# LooRollSensorMiddleBoard.net
KiCad netlist of a schematic drawn in EAGLE
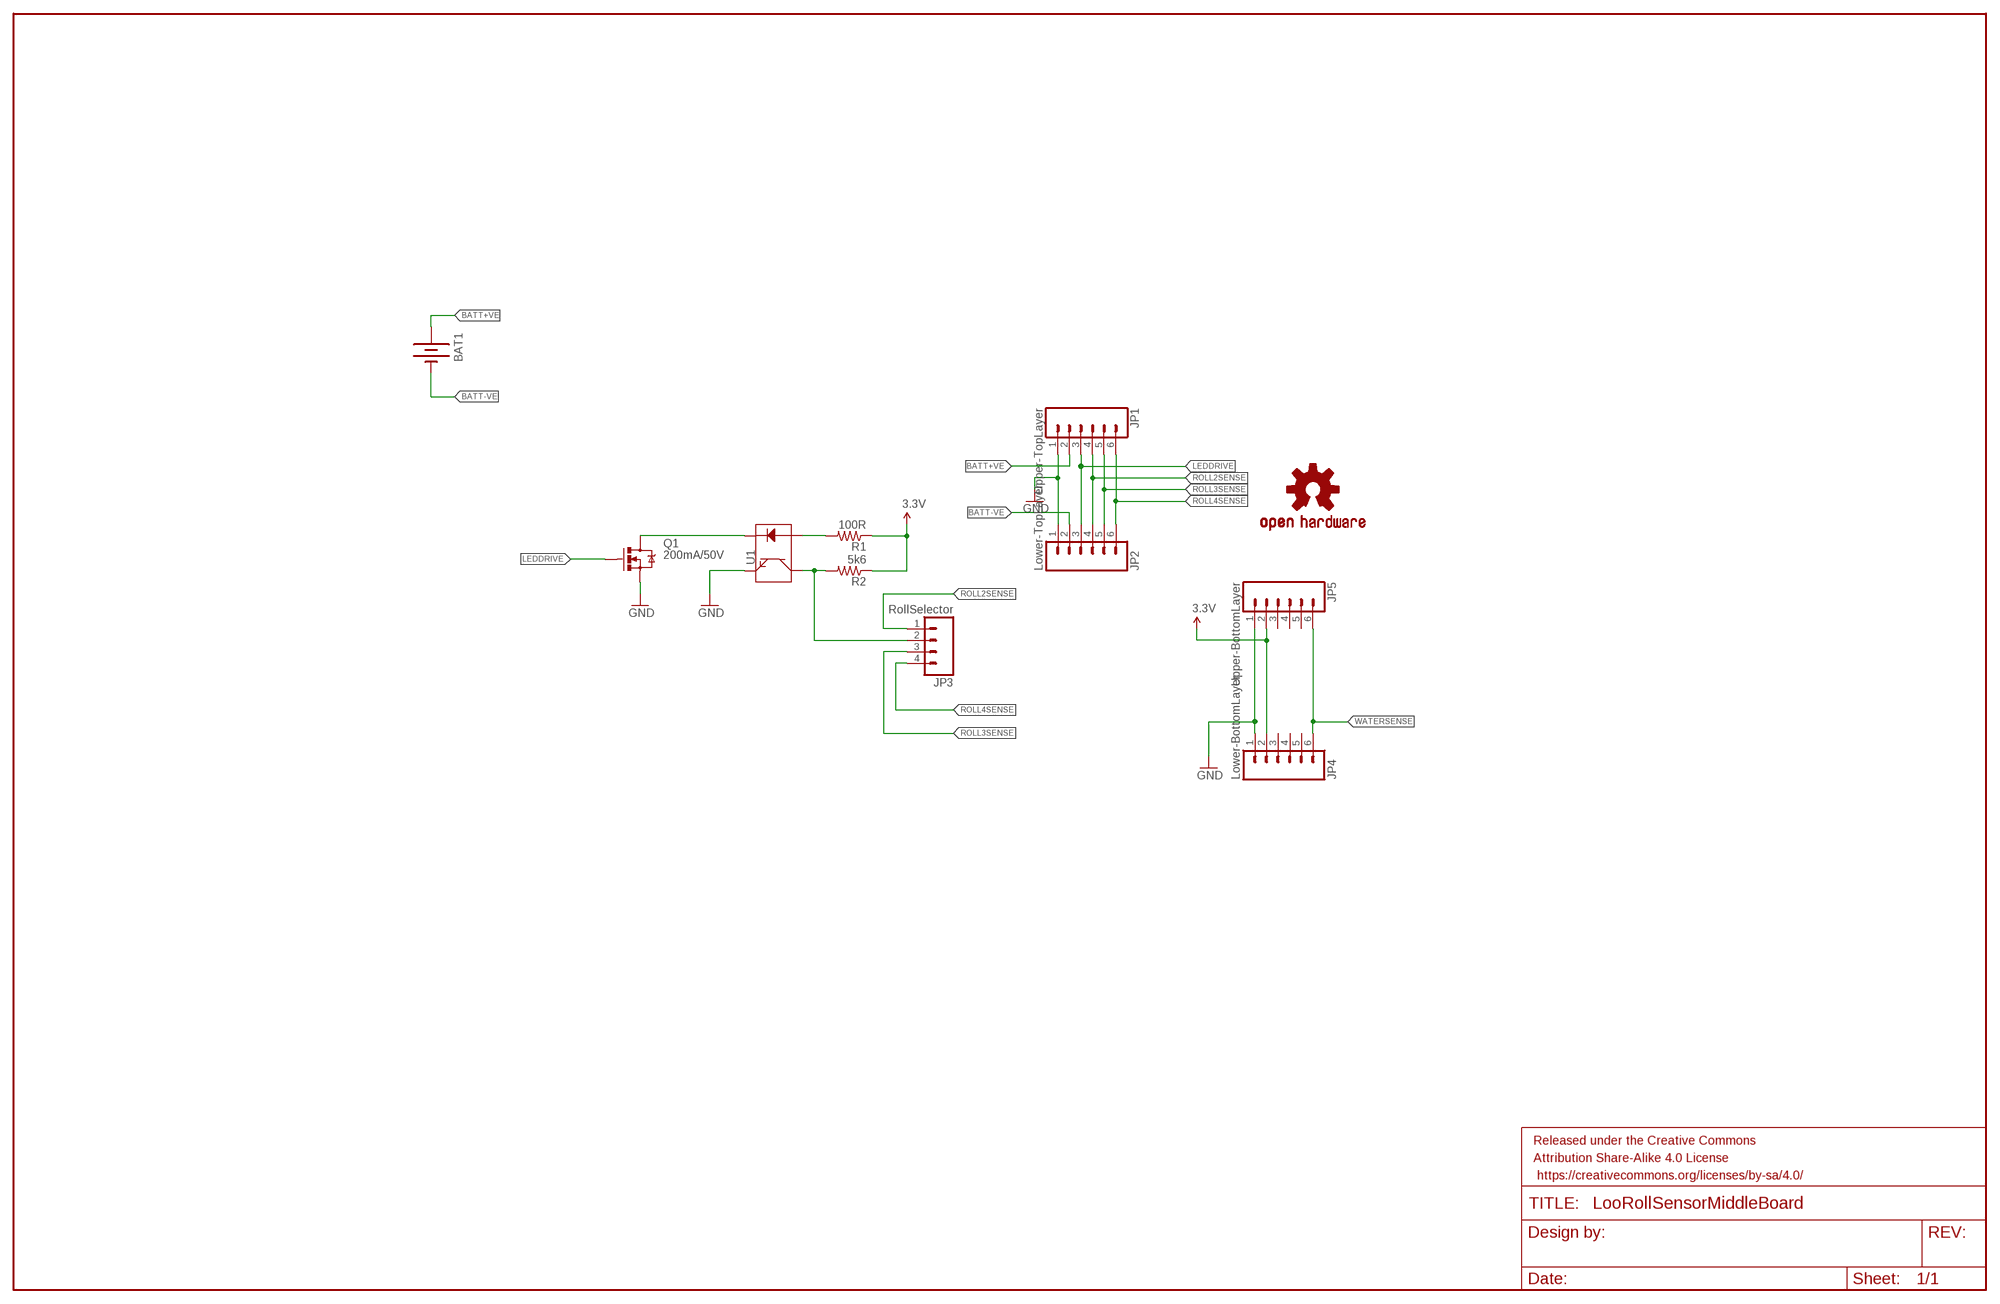
[diagram p0: schematic, sheet 1]

(export (version "E")
  (design (tool "Eeschema 10.0.6"))
  (components
    (comp (ref "BAT1")
      (value "BATTERYAA-PANEL")
      (footprint "eagle-import:BATTERY-AA-PANEL")
      (libsource (lib "eagle-import") (part "BATTERYAA-PANEL"))
    )
    (comp (ref "FRAME1")
      (value "FRAME-LEDGER")
      (footprint "eagle-import:CREATIVE_COMMONS")
      (libsource (lib "eagle-import") (part "FRAME-LEDGER"))
    )
    (comp (ref "JP1")
      (value "Upper-TopLayer")
      (footprint "eagle-import:1X06-SMD_EDGE")
      (libsource (lib "eagle-import") (part "M061X06-SMD-EDGE-SOLDERLINK1X06-SMD-EDGE-SOLDERLINK"))
    )
    (comp (ref "JP2")
      (value "Lower-TopLayer")
      (footprint "eagle-import:1X06-SMD_EDGE")
      (libsource (lib "eagle-import") (part "M061X06-SMD-EDGE-SOLDERLINK1X06-SMD-EDGE-SOLDERLINK"))
    )
    (comp (ref "JP3")
      (value "RollSelector")
      (footprint "eagle-import:1X04")
      (libsource (lib "eagle-import") (part "M04PTH"))
    )
    (comp (ref "JP4")
      (value "Lower-BottomLayer")
      (footprint "eagle-import:1X06-SMD_EDGE")
      (libsource (lib "eagle-import") (part "M061X06-SMD-EDGE-SOLDERLINK1X06-SMD-EDGE-SOLDERLINK"))
    )
    (comp (ref "JP5")
      (value "Upper-BottomLayer")
      (footprint "eagle-import:1X06-SMD_EDGE")
      (libsource (lib "eagle-import") (part "M061X06-SMD-EDGE-SOLDERLINK1X06-SMD-EDGE-SOLDERLINK"))
    )
    (comp (ref "LOGO1")
      (value "OSHW-LOGOL")
      (footprint "eagle-import:OSHW-LOGO-L")
      (libsource (lib "eagle-import") (part "OSHW-LOGOL"))
    )
    (comp (ref "Q1")
      (value "200mA/50V")
      (footprint "eagle-import:SOT23-3")
      (libsource (lib "eagle-import") (part "MOSFET-NCHANNELBSS138"))
    )
    (comp (ref "R1")
      (value "100R")
      (footprint "eagle-import:1206")
      (libsource (lib "eagle-import") (part "RESISTOR1206"))
    )
    (comp (ref "R2")
      (value "5k6")
      (footprint "eagle-import:1206")
      (libsource (lib "eagle-import") (part "RESISTOR1206"))
    )
    (comp (ref "U1")
      (value "QRE1113SMD-W")
      (footprint "eagle-import:QRE1113-W")
      (libsource (lib "eagle-import") (part "QRE1113SMD-W"))
    )
  )
  (nets
    (net (code "1") (name "3.3V") (class "Default")
      (node (ref "JP4") (pin "2") (pinfunction "2_2") (pintype "passive"))
      (node (ref "JP5") (pin "2") (pinfunction "2_2") (pintype "passive"))
      (node (ref "R1") (pin "1") (pinfunction "1_1") (pintype "passive"))
      (node (ref "R2") (pin "1") (pinfunction "1_1") (pintype "passive"))
    )
    (net (code "2") (name "BATT+VE") (class "Default")
      (node (ref "BAT1") (pin "+") (pinfunction "+_+") (pintype "power_in"))
      (node (ref "JP1") (pin "2") (pinfunction "2_2") (pintype "passive"))
    )
    (net (code "3") (name "BATT-VE") (class "Default")
      (node (ref "BAT1") (pin "-") (pinfunction "-_-") (pintype "power_in"))
      (node (ref "JP2") (pin "2") (pinfunction "2_2") (pintype "passive"))
    )
    (net (code "4") (name "GND") (class "Default")
      (node (ref "JP1") (pin "1") (pinfunction "1_1") (pintype "passive"))
      (node (ref "JP2") (pin "1") (pinfunction "1_1") (pintype "passive"))
      (node (ref "JP4") (pin "1") (pinfunction "1_1") (pintype "passive"))
      (node (ref "JP5") (pin "1") (pinfunction "1_1") (pintype "passive"))
      (node (ref "Q1") (pin "2") (pinfunction "S_2") (pintype "passive"))
      (node (ref "U1") (pin "4") (pinfunction "E_4") (pintype "bidirectional"))
    )
    (net (code "5") (name "LEDDRIVE") (class "Default")
      (node (ref "JP1") (pin "3") (pinfunction "3_3") (pintype "passive"))
      (node (ref "JP2") (pin "3") (pinfunction "3_3") (pintype "passive"))
      (node (ref "Q1") (pin "1") (pinfunction "G_1") (pintype "passive"))
    )
    (net (code "6") (name "Net-(Q1-D)") (class "Default")
      (node (ref "Q1") (pin "3") (pinfunction "D_3") (pintype "passive"))
      (node (ref "U1") (pin "2") (pinfunction "K_2") (pintype "bidirectional"))
    )
    (net (code "7") (name "Net-(U1-A)") (class "Default")
      (node (ref "R1") (pin "2") (pinfunction "2_2") (pintype "passive"))
      (node (ref "U1") (pin "1") (pinfunction "A_1") (pintype "bidirectional"))
    )
    (net (code "8") (name "Net-(U1-C)") (class "Default")
      (node (ref "JP3") (pin "2") (pinfunction "2_2") (pintype "passive"))
      (node (ref "R2") (pin "2") (pinfunction "2_2") (pintype "passive"))
      (node (ref "U1") (pin "3") (pinfunction "C_3") (pintype "bidirectional"))
    )
    (net (code "9") (name "ROLL2SENSE") (class "Default")
      (node (ref "JP1") (pin "4") (pinfunction "4_4") (pintype "passive"))
      (node (ref "JP2") (pin "4") (pinfunction "4_4") (pintype "passive"))
      (node (ref "JP3") (pin "1") (pinfunction "1_1") (pintype "passive"))
    )
    (net (code "10") (name "ROLL3SENSE") (class "Default")
      (node (ref "JP1") (pin "5") (pinfunction "5_5") (pintype "passive"))
      (node (ref "JP2") (pin "5") (pinfunction "5_5") (pintype "passive"))
      (node (ref "JP3") (pin "3") (pinfunction "3_3") (pintype "passive"))
    )
    (net (code "11") (name "ROLL4SENSE") (class "Default")
      (node (ref "JP1") (pin "6") (pinfunction "6_6") (pintype "passive"))
      (node (ref "JP2") (pin "6") (pinfunction "6_6") (pintype "passive"))
      (node (ref "JP3") (pin "4") (pinfunction "4_4") (pintype "passive"))
    )
    (net (code "12") (name "WATERSENSE") (class "Default")
      (node (ref "JP4") (pin "6") (pinfunction "6_6") (pintype "passive"))
      (node (ref "JP5") (pin "6") (pinfunction "6_6") (pintype "passive"))
    )
    (net (code "13") (name "unconnected-(JP4-Pad3)") (class "Default")
      (node (ref "JP4") (pin "3") (pinfunction "3_3") (pintype "passive"))
    )
    (net (code "14") (name "unconnected-(JP4-Pad4)") (class "Default")
      (node (ref "JP4") (pin "4") (pinfunction "4_4") (pintype "passive"))
    )
    (net (code "15") (name "unconnected-(JP4-Pad5)") (class "Default")
      (node (ref "JP4") (pin "5") (pinfunction "5_5") (pintype "passive"))
    )
    (net (code "16") (name "unconnected-(JP5-Pad3)") (class "Default")
      (node (ref "JP5") (pin "3") (pinfunction "3_3") (pintype "passive"))
    )
    (net (code "17") (name "unconnected-(JP5-Pad4)") (class "Default")
      (node (ref "JP5") (pin "4") (pinfunction "4_4") (pintype "passive"))
    )
    (net (code "18") (name "unconnected-(JP5-Pad5)") (class "Default")
      (node (ref "JP5") (pin "5") (pinfunction "5_5") (pintype "passive"))
    )
  )
)
